# AppregiatorManager.net
KiCad netlist of a schematic drawn in Altium Designer
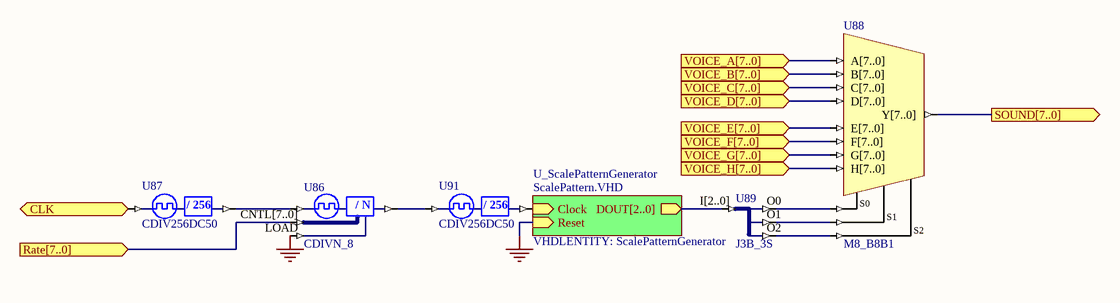
[diagram p0: AppregiatorManager.SCHDOC]

(export (version "E")
  (design (tool "Eeschema 10.0.6"))
  (components
    (comp (ref "U86")
      (value "CDIVN_8")
      (description "8-Bit Programmable Clock Divider")
      (fields (field (name "PUBLISHER") "Altium Limited"))
      (libsource (lib "FPGA Generic") (part "CDIVN_8"))
    )
    (comp (ref "U87")
      (value "CDIV256DC50")
      (description "Clock Divider by 256 with 50% Duty Cycle Output")
      (fields (field (name "PUBLISHER") "Altium Limited"))
      (libsource (lib "FPGA Generic") (part "CDIV256DC50"))
    )
    (comp (ref "U88")
      (value "M8_B8B1")
      (description "8x8-Bit Bus to 1x8-Bit Bus Multiplexer")
      (fields (field (name "PUBLISHER") "Altium Limited"))
      (libsource (lib "FPGA Generic") (part "M8_B8B1"))
    )
    (comp (ref "U89")
      (value "J3B_3S")
      (description "3-Bit input bus to 3 Single pin outputs")
      (fields (field (name "PUBLISHER") "Altium Limited"))
      (libsource (lib "FPGA Generic") (part "J3B_3S"))
    )
    (comp (ref "U91")
      (value "CDIV256DC50")
      (description "Clock Divider by 256 with 50% Duty Cycle Output")
      (fields (field (name "PUBLISHER") "Altium Limited"))
      (libsource (lib "FPGA Generic") (part "CDIV256DC50"))
    )
  )
  (nets
    (net (code "81") (name "/CLK") (class "Default")
      (node (ref "U87") (pin "CLKIN") (pinfunction "CLKIN_CLKIN") (pintype "input"))
    )
    (net (code "82") (name "/Clock") (class "Default")
      (node (ref "U91") (pin "CLKDV") (pinfunction "CLKDV_CLKDV") (pintype "output"))
    )
    (net (code "83") (name "/DOUT[2..0]") (class "Default")
      (node (ref "U89") (pin "I[2..0]") (pinfunction "I[2..0]_I[2..0]") (pintype "input"))
    )
    (net (code "84") (name "/Rate[7..0]") (class "Default")
      (node (ref "U86") (pin "CNTL[7..0]") (pinfunction "CNTL[7..0]_CNTL[7..0]") (pintype "input"))
    )
    (net (code "85") (name "/SOUND[7..0]") (class "Default")
      (node (ref "U88") (pin "Y[7..0]") (pinfunction "Y[7..0]_Y[7..0]") (pintype "output"))
    )
    (net (code "86") (name "/VOICE_A[7..0]") (class "Default")
      (node (ref "U88") (pin "A[7..0]") (pinfunction "A[7..0]_A[7..0]") (pintype "input"))
    )
    (net (code "87") (name "/VOICE_B[7..0]") (class "Default")
      (node (ref "U88") (pin "B[7..0]") (pinfunction "B[7..0]_B[7..0]") (pintype "input"))
    )
    (net (code "88") (name "/VOICE_C[7..0]") (class "Default")
      (node (ref "U88") (pin "C[7..0]") (pinfunction "C[7..0]_C[7..0]") (pintype "input"))
    )
    (net (code "89") (name "/VOICE_D[7..0]") (class "Default")
      (node (ref "U88") (pin "D[7..0]") (pinfunction "D[7..0]_D[7..0]") (pintype "input"))
    )
    (net (code "90") (name "/VOICE_E[7..0]") (class "Default")
      (node (ref "U88") (pin "E[7..0]") (pinfunction "E[7..0]_E[7..0]") (pintype "input"))
    )
    (net (code "91") (name "/VOICE_F[7..0]") (class "Default")
      (node (ref "U88") (pin "F[7..0]") (pinfunction "F[7..0]_F[7..0]") (pintype "input"))
    )
    (net (code "92") (name "/VOICE_G[7..0]") (class "Default")
      (node (ref "U88") (pin "G[7..0]") (pinfunction "G[7..0]_G[7..0]") (pintype "input"))
    )
    (net (code "93") (name "/VOICE_H[7..0]") (class "Default")
      (node (ref "U88") (pin "H[7..0]") (pinfunction "H[7..0]_H[7..0]") (pintype "input"))
    )
    (net (code "94") (name "GND") (class "Default")
      (node (ref "U86") (pin "LOAD") (pinfunction "LOAD_LOAD") (pintype "input"))
    )
    (net (code "95") (name "Net-(U86-PadCLKDV)") (class "Default")
      (node (ref "U86") (pin "CLKDV") (pinfunction "CLKDV_CLKDV") (pintype "output"))
      (node (ref "U91") (pin "CLKIN") (pinfunction "CLKIN_CLKIN") (pintype "input"))
    )
    (net (code "96") (name "Net-(U86-PadCLKIN)") (class "Default")
      (node (ref "U86") (pin "CLKIN") (pinfunction "CLKIN_CLKIN") (pintype "input"))
      (node (ref "U87") (pin "CLKDV") (pinfunction "CLKDV_CLKDV") (pintype "output"))
    )
    (net (code "97") (name "Net-(U88-PadS0)") (class "Default")
      (node (ref "U88") (pin "S0") (pinfunction "S0_S0") (pintype "input"))
      (node (ref "U89") (pin "O0") (pinfunction "O0_O0") (pintype "output"))
    )
    (net (code "98") (name "Net-(U88-PadS1)") (class "Default")
      (node (ref "U88") (pin "S1") (pinfunction "S1_S1") (pintype "input"))
      (node (ref "U89") (pin "O1") (pinfunction "O1_O1") (pintype "output"))
    )
    (net (code "99") (name "Net-(U88-PadS2)") (class "Default")
      (node (ref "U88") (pin "S2") (pinfunction "S2_S2") (pintype "input"))
      (node (ref "U89") (pin "O2") (pinfunction "O2_O2") (pintype "output"))
    )
  )
)
